# mini-DINs.net
KiCad netlist of a schematic drawn in Altium Designer
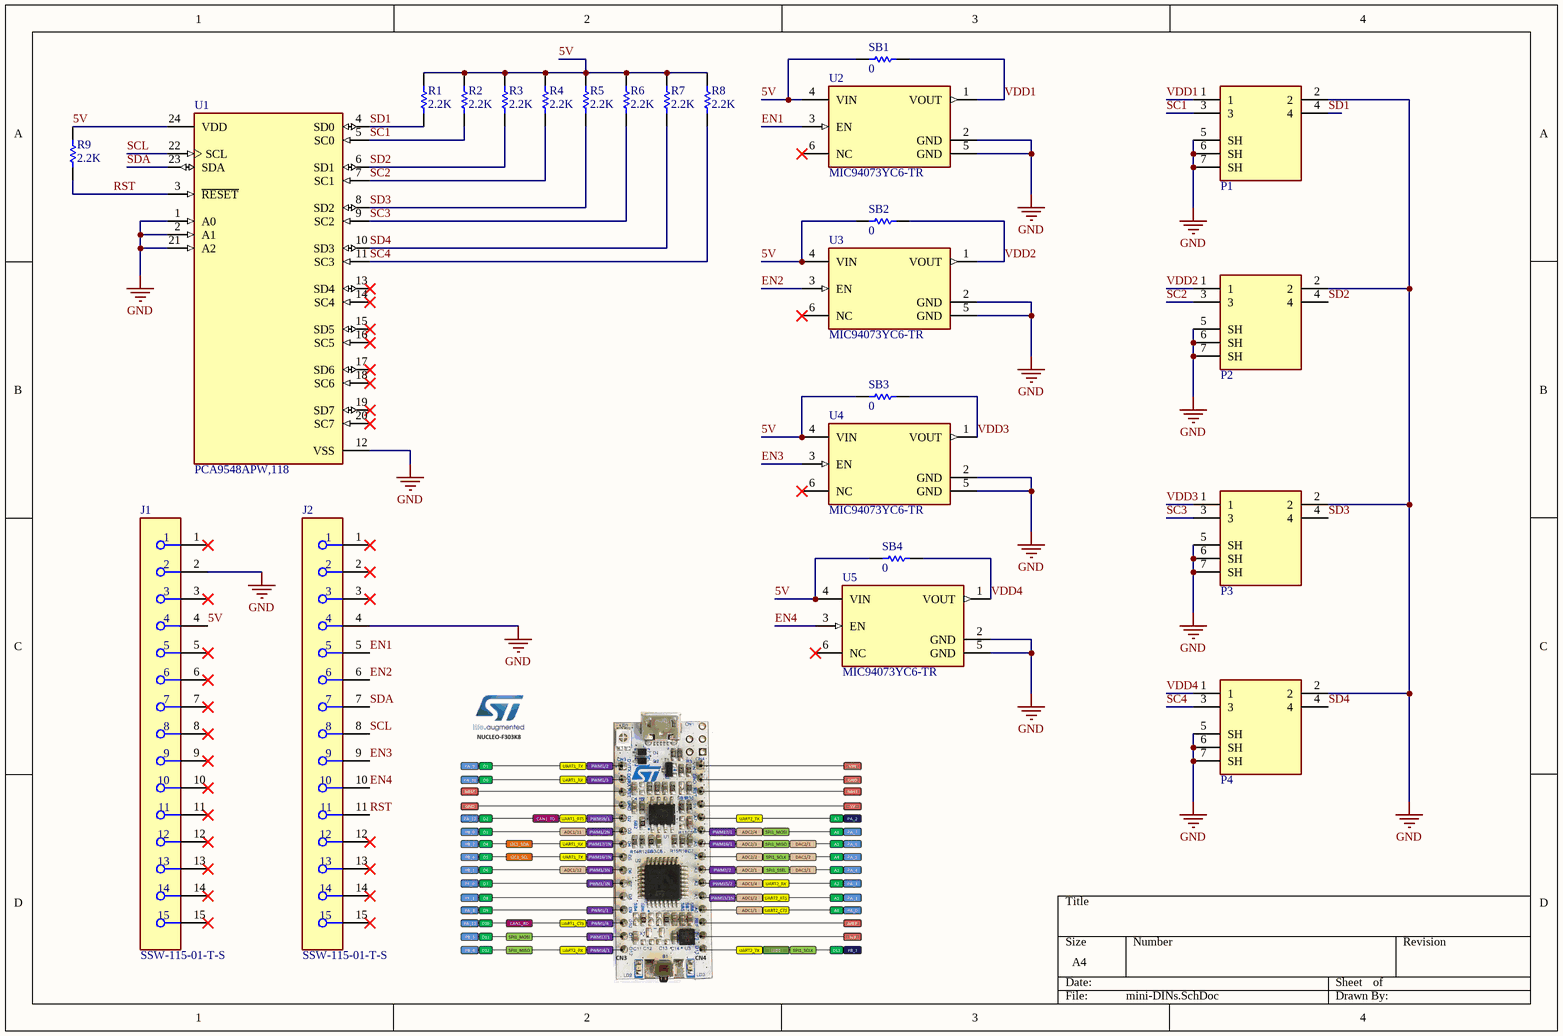
[diagram p0: mini-DINs.SchDoc]

(export (version "E")
  (design (tool "Eeschema 10.0.6"))
  (components
    (comp (ref "J1")
      (value "SSW-115-01-T-S")
      (footprint "FP-SSW-115-01-T-S-MFG")
      (description "CONN RCPT 15POS 0.1 TIN PCB")
      (libsource (lib "Altium Content Vault") (part "de2cdd76613f87adcba81301aaab7e9"))
    )
    (comp (ref "J2")
      (value "SSW-115-01-T-S")
      (footprint "FP-SSW-115-01-T-S-MFG")
      (description "CONN RCPT 15POS 0.1 TIN PCB")
      (libsource (lib "Altium Content Vault") (part "de2cdd76613f87adcba81301aaab7e9"))
    )
    (comp (ref "P1")
      (value "mini-DIN-connector")
      (footprint "TE_5749181-1")
      (description "https://dk.rs-online.com/web/p/din-stik/1644205?gb=s")
      (libsource (lib "mySchLib") (part "mini-DIN-connector"))
    )
    (comp (ref "P2")
      (value "mini-DIN-connector")
      (footprint "TE_5749181-1")
      (description "https://dk.rs-online.com/web/p/din-stik/1644205?gb=s")
      (libsource (lib "mySchLib") (part "mini-DIN-connector"))
    )
    (comp (ref "P3")
      (value "mini-DIN-connector")
      (footprint "TE_5749181-1")
      (description "https://dk.rs-online.com/web/p/din-stik/1644205?gb=s")
      (libsource (lib "mySchLib") (part "mini-DIN-connector"))
    )
    (comp (ref "P4")
      (value "mini-DIN-connector")
      (footprint "TE_5749181-1")
      (description "https://dk.rs-online.com/web/p/din-stik/1644205?gb=s")
      (libsource (lib "mySchLib") (part "mini-DIN-connector"))
    )
    (comp (ref "R1")
      (value "2.2K")
      (footprint "RESC1608X55X25ML10T15")
      (description "Chip Resistor, 0 Ohm, +/- 5%, 0.1 W, -55 to 155 degC, 0603 (1608 Metric), RoHS, Tape and Reel")
      (fields (field (name "TOLERANCE") "5%") (field (name "MANUFACTURER") "Yageo"))
      (libsource (lib "Altium Content Vault") (part "RES-2"))
    )
    (comp (ref "R2")
      (value "2.2K")
      (footprint "RESC1608X55X25ML10T15")
      (description "Chip Resistor, 0 Ohm, +/- 5%, 0.1 W, -55 to 155 degC, 0603 (1608 Metric), RoHS, Tape and Reel")
      (fields (field (name "TOLERANCE") "5%") (field (name "MANUFACTURER") "Yageo"))
      (libsource (lib "Altium Content Vault") (part "RES-2"))
    )
    (comp (ref "R3")
      (value "2.2K")
      (footprint "RESC1608X55X25ML10T15")
      (description "Chip Resistor, 0 Ohm, +/- 5%, 0.1 W, -55 to 155 degC, 0603 (1608 Metric), RoHS, Tape and Reel")
      (fields (field (name "TOLERANCE") "5%") (field (name "MANUFACTURER") "Yageo"))
      (libsource (lib "Altium Content Vault") (part "RES-2"))
    )
    (comp (ref "R4")
      (value "2.2K")
      (footprint "RESC1608X55X25ML10T15")
      (description "Chip Resistor, 0 Ohm, +/- 5%, 0.1 W, -55 to 155 degC, 0603 (1608 Metric), RoHS, Tape and Reel")
      (fields (field (name "TOLERANCE") "5%") (field (name "MANUFACTURER") "Yageo"))
      (libsource (lib "Altium Content Vault") (part "RES-2"))
    )
    (comp (ref "R5")
      (value "2.2K")
      (footprint "RESC1608X55X25ML10T15")
      (description "Chip Resistor, 0 Ohm, +/- 5%, 0.1 W, -55 to 155 degC, 0603 (1608 Metric), RoHS, Tape and Reel")
      (fields (field (name "TOLERANCE") "5%") (field (name "MANUFACTURER") "Yageo"))
      (libsource (lib "Altium Content Vault") (part "RES-2"))
    )
    (comp (ref "R6")
      (value "2.2K")
      (footprint "RESC1608X55X25ML10T15")
      (description "Chip Resistor, 0 Ohm, +/- 5%, 0.1 W, -55 to 155 degC, 0603 (1608 Metric), RoHS, Tape and Reel")
      (fields (field (name "TOLERANCE") "5%") (field (name "MANUFACTURER") "Yageo"))
      (libsource (lib "Altium Content Vault") (part "RES-2"))
    )
    (comp (ref "R7")
      (value "2.2K")
      (footprint "RESC1608X55X25ML10T15")
      (description "Chip Resistor, 0 Ohm, +/- 5%, 0.1 W, -55 to 155 degC, 0603 (1608 Metric), RoHS, Tape and Reel")
      (fields (field (name "TOLERANCE") "5%") (field (name "MANUFACTURER") "Yageo"))
      (libsource (lib "Altium Content Vault") (part "RES-2"))
    )
    (comp (ref "R8")
      (value "2.2K")
      (footprint "RESC1608X55X25ML10T15")
      (description "Chip Resistor, 0 Ohm, +/- 5%, 0.1 W, -55 to 155 degC, 0603 (1608 Metric), RoHS, Tape and Reel")
      (fields (field (name "TOLERANCE") "5%") (field (name "MANUFACTURER") "Yageo"))
      (libsource (lib "Altium Content Vault") (part "RES-2"))
    )
    (comp (ref "R9")
      (value "2.2K")
      (footprint "RESC1608X55X25ML10T15")
      (description "Chip Resistor, 0 Ohm, +/- 5%, 0.1 W, -55 to 155 degC, 0603 (1608 Metric), RoHS, Tape and Reel")
      (fields (field (name "TOLERANCE") "5%") (field (name "MANUFACTURER") "Yageo"))
      (libsource (lib "Altium Content Vault") (part "RES-2"))
    )
    (comp (ref "SB1")
      (value "0")
      (footprint "RESC1608X55X25ML10T15")
      (description "Chip Resistor, 0 Ohm, +/- 5%, 0.1 W, -55 to 155 degC, 0603 (1608 Metric), RoHS, Tape and Reel")
      (fields (field (name "TOLERANCE") "5%") (field (name "MANUFACTURER") "Yageo"))
      (libsource (lib "Altium Content Vault") (part "RES-2"))
    )
    (comp (ref "SB2")
      (value "0")
      (footprint "RESC1608X55X25ML10T15")
      (description "Chip Resistor, 0 Ohm, +/- 5%, 0.1 W, -55 to 155 degC, 0603 (1608 Metric), RoHS, Tape and Reel")
      (fields (field (name "TOLERANCE") "5%") (field (name "MANUFACTURER") "Yageo"))
      (libsource (lib "Altium Content Vault") (part "RES-2"))
    )
    (comp (ref "SB3")
      (value "0")
      (footprint "RESC1608X55X25ML10T15")
      (description "Chip Resistor, 0 Ohm, +/- 5%, 0.1 W, -55 to 155 degC, 0603 (1608 Metric), RoHS, Tape and Reel")
      (fields (field (name "TOLERANCE") "5%") (field (name "MANUFACTURER") "Yageo"))
      (libsource (lib "Altium Content Vault") (part "RES-2"))
    )
    (comp (ref "SB4")
      (value "0")
      (footprint "RESC1608X55X25ML10T15")
      (description "Chip Resistor, 0 Ohm, +/- 5%, 0.1 W, -55 to 155 degC, 0603 (1608 Metric), RoHS, Tape and Reel")
      (fields (field (name "TOLERANCE") "5%") (field (name "MANUFACTURER") "Yageo"))
      (libsource (lib "Altium Content Vault") (part "RES-2"))
    )
    (comp (ref "U1")
      (value "PCA9548APW,118")
      (footprint "FP-SOT355-1-MFG")
      (description "IC INTERFACE SPECIALIZED 24TSSOP")
      (libsource (lib "Altium Content Vault") (part "3e168d29e2cae1e9eb34f21911d2ccb"))
    )
    (comp (ref "U2")
      (value "MIC94073YC6-TR")
      (footprint "FP-SC70-6LD-PL-1-IPC_B")
      (description "IC PWR SWITCH P-CHAN 1:1 SC70-6")
      (fields (field (name "VOLTAGE") "5.5V"))
      (libsource (lib "Altium Content Vault") (part "576ca0c7f0c3b0be23749db0ef6e4d8"))
    )
    (comp (ref "U3")
      (value "MIC94073YC6-TR")
      (footprint "FP-SC70-6LD-PL-1-IPC_B")
      (description "IC PWR SWITCH P-CHAN 1:1 SC70-6")
      (fields (field (name "VOLTAGE") "5.5V"))
      (libsource (lib "Altium Content Vault") (part "576ca0c7f0c3b0be23749db0ef6e4d8"))
    )
    (comp (ref "U4")
      (value "MIC94073YC6-TR")
      (footprint "FP-SC70-6LD-PL-1-IPC_B")
      (description "IC PWR SWITCH P-CHAN 1:1 SC70-6")
      (fields (field (name "VOLTAGE") "5.5V"))
      (libsource (lib "Altium Content Vault") (part "576ca0c7f0c3b0be23749db0ef6e4d8"))
    )
    (comp (ref "U5")
      (value "MIC94073YC6-TR")
      (footprint "FP-SC70-6LD-PL-1-IPC_B")
      (description "IC PWR SWITCH P-CHAN 1:1 SC70-6")
      (fields (field (name "VOLTAGE") "5.5V"))
      (libsource (lib "Altium Content Vault") (part "576ca0c7f0c3b0be23749db0ef6e4d8"))
    )
  )
  (nets
    (net (code "1") (name "/5V") (class "Default")
      (node (ref "J1") (pin "4") (pinfunction "4_4") (pintype "passive"))
      (node (ref "R1") (pin "2") (pinfunction "2_2") (pintype "passive"))
      (node (ref "R2") (pin "2") (pinfunction "2_2") (pintype "passive"))
      (node (ref "R3") (pin "2") (pinfunction "2_2") (pintype "passive"))
      (node (ref "R4") (pin "2") (pinfunction "2_2") (pintype "passive"))
      (node (ref "R5") (pin "2") (pinfunction "2_2") (pintype "passive"))
      (node (ref "R6") (pin "2") (pinfunction "2_2") (pintype "passive"))
      (node (ref "R7") (pin "2") (pinfunction "2_2") (pintype "passive"))
      (node (ref "R8") (pin "2") (pinfunction "2_2") (pintype "passive"))
      (node (ref "R9") (pin "2") (pinfunction "2_2") (pintype "passive"))
      (node (ref "SB1") (pin "2") (pinfunction "2_2") (pintype "passive"))
      (node (ref "SB2") (pin "2") (pinfunction "2_2") (pintype "passive"))
      (node (ref "SB3") (pin "2") (pinfunction "2_2") (pintype "passive"))
      (node (ref "SB4") (pin "2") (pinfunction "2_2") (pintype "passive"))
      (node (ref "U1") (pin "24") (pinfunction "VDD_24") (pintype "power_in"))
      (node (ref "U2") (pin "4") (pinfunction "VIN_4") (pintype "power_in"))
      (node (ref "U3") (pin "4") (pinfunction "VIN_4") (pintype "power_in"))
      (node (ref "U4") (pin "4") (pinfunction "VIN_4") (pintype "power_in"))
      (node (ref "U5") (pin "4") (pinfunction "VIN_4") (pintype "power_in"))
    )
    (net (code "2") (name "/EN1") (class "Default")
      (node (ref "J2") (pin "5") (pinfunction "5_5") (pintype "passive"))
      (node (ref "U2") (pin "3") (pinfunction "EN_3") (pintype "input"))
    )
    (net (code "3") (name "/EN2") (class "Default")
      (node (ref "J2") (pin "6") (pinfunction "6_6") (pintype "passive"))
      (node (ref "U3") (pin "3") (pinfunction "EN_3") (pintype "input"))
    )
    (net (code "4") (name "/EN3") (class "Default")
      (node (ref "J2") (pin "9") (pinfunction "9_9") (pintype "passive"))
      (node (ref "U4") (pin "3") (pinfunction "EN_3") (pintype "input"))
    )
    (net (code "5") (name "/EN4") (class "Default")
      (node (ref "J2") (pin "10") (pinfunction "10_10") (pintype "passive"))
      (node (ref "U5") (pin "3") (pinfunction "EN_3") (pintype "input"))
    )
    (net (code "6") (name "/RST") (class "Default")
      (node (ref "J2") (pin "11") (pinfunction "11_11") (pintype "passive"))
      (node (ref "R9") (pin "1") (pinfunction "1_1") (pintype "passive"))
      (node (ref "U1") (pin "3") (pinfunction "~{RESET}_3") (pintype "input"))
    )
    (net (code "7") (name "/SC1") (class "Default")
      (node (ref "P1") (pin "3") (pinfunction "3_3") (pintype "passive"))
      (node (ref "R2") (pin "1") (pinfunction "1_1") (pintype "passive"))
      (node (ref "U1") (pin "5") (pinfunction "SC0_5") (pintype "input"))
    )
    (net (code "8") (name "/SC2") (class "Default")
      (node (ref "P2") (pin "3") (pinfunction "3_3") (pintype "passive"))
      (node (ref "R4") (pin "1") (pinfunction "1_1") (pintype "passive"))
      (node (ref "U1") (pin "7") (pinfunction "SC1_7") (pintype "input"))
    )
    (net (code "9") (name "/SC3") (class "Default")
      (node (ref "P3") (pin "3") (pinfunction "3_3") (pintype "passive"))
      (node (ref "R6") (pin "1") (pinfunction "1_1") (pintype "passive"))
      (node (ref "U1") (pin "9") (pinfunction "SC2_9") (pintype "input"))
    )
    (net (code "10") (name "/SC4") (class "Default")
      (node (ref "P4") (pin "3") (pinfunction "3_3") (pintype "passive"))
      (node (ref "R8") (pin "1") (pinfunction "1_1") (pintype "passive"))
      (node (ref "U1") (pin "11") (pinfunction "SC3_11") (pintype "input"))
    )
    (net (code "11") (name "/SCL") (class "Default")
      (node (ref "J2") (pin "8") (pinfunction "8_8") (pintype "passive"))
      (node (ref "U1") (pin "22") (pinfunction "SCL_22") (pintype "input"))
    )
    (net (code "12") (name "/SD1") (class "Default")
      (node (ref "P1") (pin "4") (pinfunction "4_4") (pintype "passive"))
      (node (ref "R1") (pin "1") (pinfunction "1_1") (pintype "passive"))
      (node (ref "U1") (pin "4") (pinfunction "SD0_4") (pintype "bidirectional"))
    )
    (net (code "13") (name "/SD2") (class "Default")
      (node (ref "P2") (pin "4") (pinfunction "4_4") (pintype "passive"))
      (node (ref "R3") (pin "1") (pinfunction "1_1") (pintype "passive"))
      (node (ref "U1") (pin "6") (pinfunction "SD1_6") (pintype "bidirectional"))
    )
    (net (code "14") (name "/SD3") (class "Default")
      (node (ref "P3") (pin "4") (pinfunction "4_4") (pintype "passive"))
      (node (ref "R5") (pin "1") (pinfunction "1_1") (pintype "passive"))
      (node (ref "U1") (pin "8") (pinfunction "SD2_8") (pintype "bidirectional"))
    )
    (net (code "15") (name "/SD4") (class "Default")
      (node (ref "P4") (pin "4") (pinfunction "4_4") (pintype "passive"))
      (node (ref "R7") (pin "1") (pinfunction "1_1") (pintype "passive"))
      (node (ref "U1") (pin "10") (pinfunction "SD3_10") (pintype "bidirectional"))
    )
    (net (code "16") (name "/SDA") (class "Default")
      (node (ref "J2") (pin "7") (pinfunction "7_7") (pintype "passive"))
      (node (ref "U1") (pin "23") (pinfunction "SDA_23") (pintype "bidirectional"))
    )
    (net (code "17") (name "/VDD1") (class "Default")
      (node (ref "P1") (pin "1") (pinfunction "1_1") (pintype "passive"))
      (node (ref "SB1") (pin "1") (pinfunction "1_1") (pintype "passive"))
      (node (ref "U2") (pin "1") (pinfunction "VOUT_1") (pintype "output"))
    )
    (net (code "18") (name "/VDD2") (class "Default")
      (node (ref "P2") (pin "1") (pinfunction "1_1") (pintype "passive"))
      (node (ref "SB2") (pin "1") (pinfunction "1_1") (pintype "passive"))
      (node (ref "U3") (pin "1") (pinfunction "VOUT_1") (pintype "output"))
    )
    (net (code "19") (name "/VDD3") (class "Default")
      (node (ref "P3") (pin "1") (pinfunction "1_1") (pintype "passive"))
      (node (ref "SB3") (pin "1") (pinfunction "1_1") (pintype "passive"))
      (node (ref "U4") (pin "1") (pinfunction "VOUT_1") (pintype "output"))
    )
    (net (code "20") (name "/VDD4") (class "Default")
      (node (ref "P4") (pin "1") (pinfunction "1_1") (pintype "passive"))
      (node (ref "SB4") (pin "1") (pinfunction "1_1") (pintype "passive"))
      (node (ref "U5") (pin "1") (pinfunction "VOUT_1") (pintype "output"))
    )
    (net (code "21") (name "GND") (class "Default")
      (node (ref "J1") (pin "2") (pinfunction "2_2") (pintype "passive"))
      (node (ref "J2") (pin "4") (pinfunction "4_4") (pintype "passive"))
      (node (ref "P1") (pin "2") (pinfunction "2_2") (pintype "passive"))
      (node (ref "P1") (pin "5") (pinfunction "SH_5") (pintype "passive"))
      (node (ref "P1") (pin "6") (pinfunction "SH_6") (pintype "passive"))
      (node (ref "P1") (pin "7") (pinfunction "SH_7") (pintype "passive"))
      (node (ref "P2") (pin "2") (pinfunction "2_2") (pintype "passive"))
      (node (ref "P2") (pin "5") (pinfunction "SH_5") (pintype "passive"))
      (node (ref "P2") (pin "6") (pinfunction "SH_6") (pintype "passive"))
      (node (ref "P2") (pin "7") (pinfunction "SH_7") (pintype "passive"))
      (node (ref "P3") (pin "2") (pinfunction "2_2") (pintype "passive"))
      (node (ref "P3") (pin "5") (pinfunction "SH_5") (pintype "passive"))
      (node (ref "P3") (pin "6") (pinfunction "SH_6") (pintype "passive"))
      (node (ref "P3") (pin "7") (pinfunction "SH_7") (pintype "passive"))
      (node (ref "P4") (pin "2") (pinfunction "2_2") (pintype "passive"))
      (node (ref "P4") (pin "5") (pinfunction "SH_5") (pintype "passive"))
      (node (ref "P4") (pin "6") (pinfunction "SH_6") (pintype "passive"))
      (node (ref "P4") (pin "7") (pinfunction "SH_7") (pintype "passive"))
      (node (ref "U1") (pin "1") (pinfunction "A0_1") (pintype "input"))
      (node (ref "U1") (pin "12") (pinfunction "VSS_12") (pintype "power_in"))
      (node (ref "U1") (pin "2") (pinfunction "A1_2") (pintype "input"))
      (node (ref "U1") (pin "21") (pinfunction "A2_21") (pintype "input"))
      (node (ref "U2") (pin "2") (pinfunction "GND_2") (pintype "power_in"))
      (node (ref "U2") (pin "5") (pinfunction "GND_5") (pintype "power_in"))
      (node (ref "U3") (pin "2") (pinfunction "GND_2") (pintype "power_in"))
      (node (ref "U3") (pin "5") (pinfunction "GND_5") (pintype "power_in"))
      (node (ref "U4") (pin "2") (pinfunction "GND_2") (pintype "power_in"))
      (node (ref "U4") (pin "5") (pinfunction "GND_5") (pintype "power_in"))
      (node (ref "U5") (pin "2") (pinfunction "GND_2") (pintype "power_in"))
      (node (ref "U5") (pin "5") (pinfunction "GND_5") (pintype "power_in"))
    )
    (net (code "22") (name "unconnected-(J1-Pad1)") (class "Default")
      (node (ref "J1") (pin "1") (pinfunction "1_1") (pintype "passive+no_connect"))
    )
    (net (code "23") (name "unconnected-(J1-Pad3)") (class "Default")
      (node (ref "J1") (pin "3") (pinfunction "3_3") (pintype "passive+no_connect"))
    )
    (net (code "24") (name "unconnected-(J1-Pad5)") (class "Default")
      (node (ref "J1") (pin "5") (pinfunction "5_5") (pintype "passive+no_connect"))
    )
    (net (code "25") (name "unconnected-(J1-Pad6)") (class "Default")
      (node (ref "J1") (pin "6") (pinfunction "6_6") (pintype "passive+no_connect"))
    )
    (net (code "26") (name "unconnected-(J1-Pad7)") (class "Default")
      (node (ref "J1") (pin "7") (pinfunction "7_7") (pintype "passive+no_connect"))
    )
    (net (code "27") (name "unconnected-(J1-Pad8)") (class "Default")
      (node (ref "J1") (pin "8") (pinfunction "8_8") (pintype "passive+no_connect"))
    )
    (net (code "28") (name "unconnected-(J1-Pad9)") (class "Default")
      (node (ref "J1") (pin "9") (pinfunction "9_9") (pintype "passive+no_connect"))
    )
    (net (code "29") (name "unconnected-(J1-Pad10)") (class "Default")
      (node (ref "J1") (pin "10") (pinfunction "10_10") (pintype "passive+no_connect"))
    )
    (net (code "30") (name "unconnected-(J1-Pad11)") (class "Default")
      (node (ref "J1") (pin "11") (pinfunction "11_11") (pintype "passive+no_connect"))
    )
    (net (code "31") (name "unconnected-(J1-Pad12)") (class "Default")
      (node (ref "J1") (pin "12") (pinfunction "12_12") (pintype "passive+no_connect"))
    )
    (net (code "32") (name "unconnected-(J1-Pad13)") (class "Default")
      (node (ref "J1") (pin "13") (pinfunction "13_13") (pintype "passive+no_connect"))
    )
    (net (code "33") (name "unconnected-(J1-Pad14)") (class "Default")
      (node (ref "J1") (pin "14") (pinfunction "14_14") (pintype "passive+no_connect"))
    )
    (net (code "34") (name "unconnected-(J1-Pad15)") (class "Default")
      (node (ref "J1") (pin "15") (pinfunction "15_15") (pintype "passive+no_connect"))
    )
    (net (code "35") (name "unconnected-(J2-Pad1)") (class "Default")
      (node (ref "J2") (pin "1") (pinfunction "1_1") (pintype "passive+no_connect"))
    )
    (net (code "36") (name "unconnected-(J2-Pad2)") (class "Default")
      (node (ref "J2") (pin "2") (pinfunction "2_2") (pintype "passive+no_connect"))
    )
    (net (code "37") (name "unconnected-(J2-Pad3)") (class "Default")
      (node (ref "J2") (pin "3") (pinfunction "3_3") (pintype "passive+no_connect"))
    )
    (net (code "38") (name "unconnected-(J2-Pad12)") (class "Default")
      (node (ref "J2") (pin "12") (pinfunction "12_12") (pintype "passive+no_connect"))
    )
    (net (code "39") (name "unconnected-(J2-Pad13)") (class "Default")
      (node (ref "J2") (pin "13") (pinfunction "13_13") (pintype "passive+no_connect"))
    )
    (net (code "40") (name "unconnected-(J2-Pad14)") (class "Default")
      (node (ref "J2") (pin "14") (pinfunction "14_14") (pintype "passive+no_connect"))
    )
    (net (code "41") (name "unconnected-(J2-Pad15)") (class "Default")
      (node (ref "J2") (pin "15") (pinfunction "15_15") (pintype "passive+no_connect"))
    )
    (net (code "42") (name "unconnected-(U1-SC4-Pad14)") (class "Default")
      (node (ref "U1") (pin "14") (pinfunction "SC4_14") (pintype "input+no_connect"))
    )
    (net (code "43") (name "unconnected-(U1-SC5-Pad16)") (class "Default")
      (node (ref "U1") (pin "16") (pinfunction "SC5_16") (pintype "input+no_connect"))
    )
    (net (code "44") (name "unconnected-(U1-SC6-Pad18)") (class "Default")
      (node (ref "U1") (pin "18") (pinfunction "SC6_18") (pintype "input+no_connect"))
    )
    (net (code "45") (name "unconnected-(U1-SC7-Pad20)") (class "Default")
      (node (ref "U1") (pin "20") (pinfunction "SC7_20") (pintype "input+no_connect"))
    )
    (net (code "46") (name "unconnected-(U1-SD4-Pad13)") (class "Default")
      (node (ref "U1") (pin "13") (pinfunction "SD4_13") (pintype "bidirectional+no_connect"))
    )
    (net (code "47") (name "unconnected-(U1-SD5-Pad15)") (class "Default")
      (node (ref "U1") (pin "15") (pinfunction "SD5_15") (pintype "bidirectional+no_connect"))
    )
    (net (code "48") (name "unconnected-(U1-SD6-Pad17)") (class "Default")
      (node (ref "U1") (pin "17") (pinfunction "SD6_17") (pintype "bidirectional+no_connect"))
    )
    (net (code "49") (name "unconnected-(U1-SD7-Pad19)") (class "Default")
      (node (ref "U1") (pin "19") (pinfunction "SD7_19") (pintype "bidirectional+no_connect"))
    )
    (net (code "50") (name "unconnected-(U2-NC-Pad6)") (class "Default")
      (node (ref "U2") (pin "6") (pinfunction "NC_6") (pintype "passive+no_connect"))
    )
    (net (code "51") (name "unconnected-(U3-NC-Pad6)") (class "Default")
      (node (ref "U3") (pin "6") (pinfunction "NC_6") (pintype "passive+no_connect"))
    )
    (net (code "52") (name "unconnected-(U4-NC-Pad6)") (class "Default")
      (node (ref "U4") (pin "6") (pinfunction "NC_6") (pintype "passive+no_connect"))
    )
    (net (code "53") (name "unconnected-(U5-NC-Pad6)") (class "Default")
      (node (ref "U5") (pin "6") (pinfunction "NC_6") (pintype "passive+no_connect"))
    )
  )
)
